# lpf-5th-order.net
KiCad netlist of a schematic drawn in EAGLE
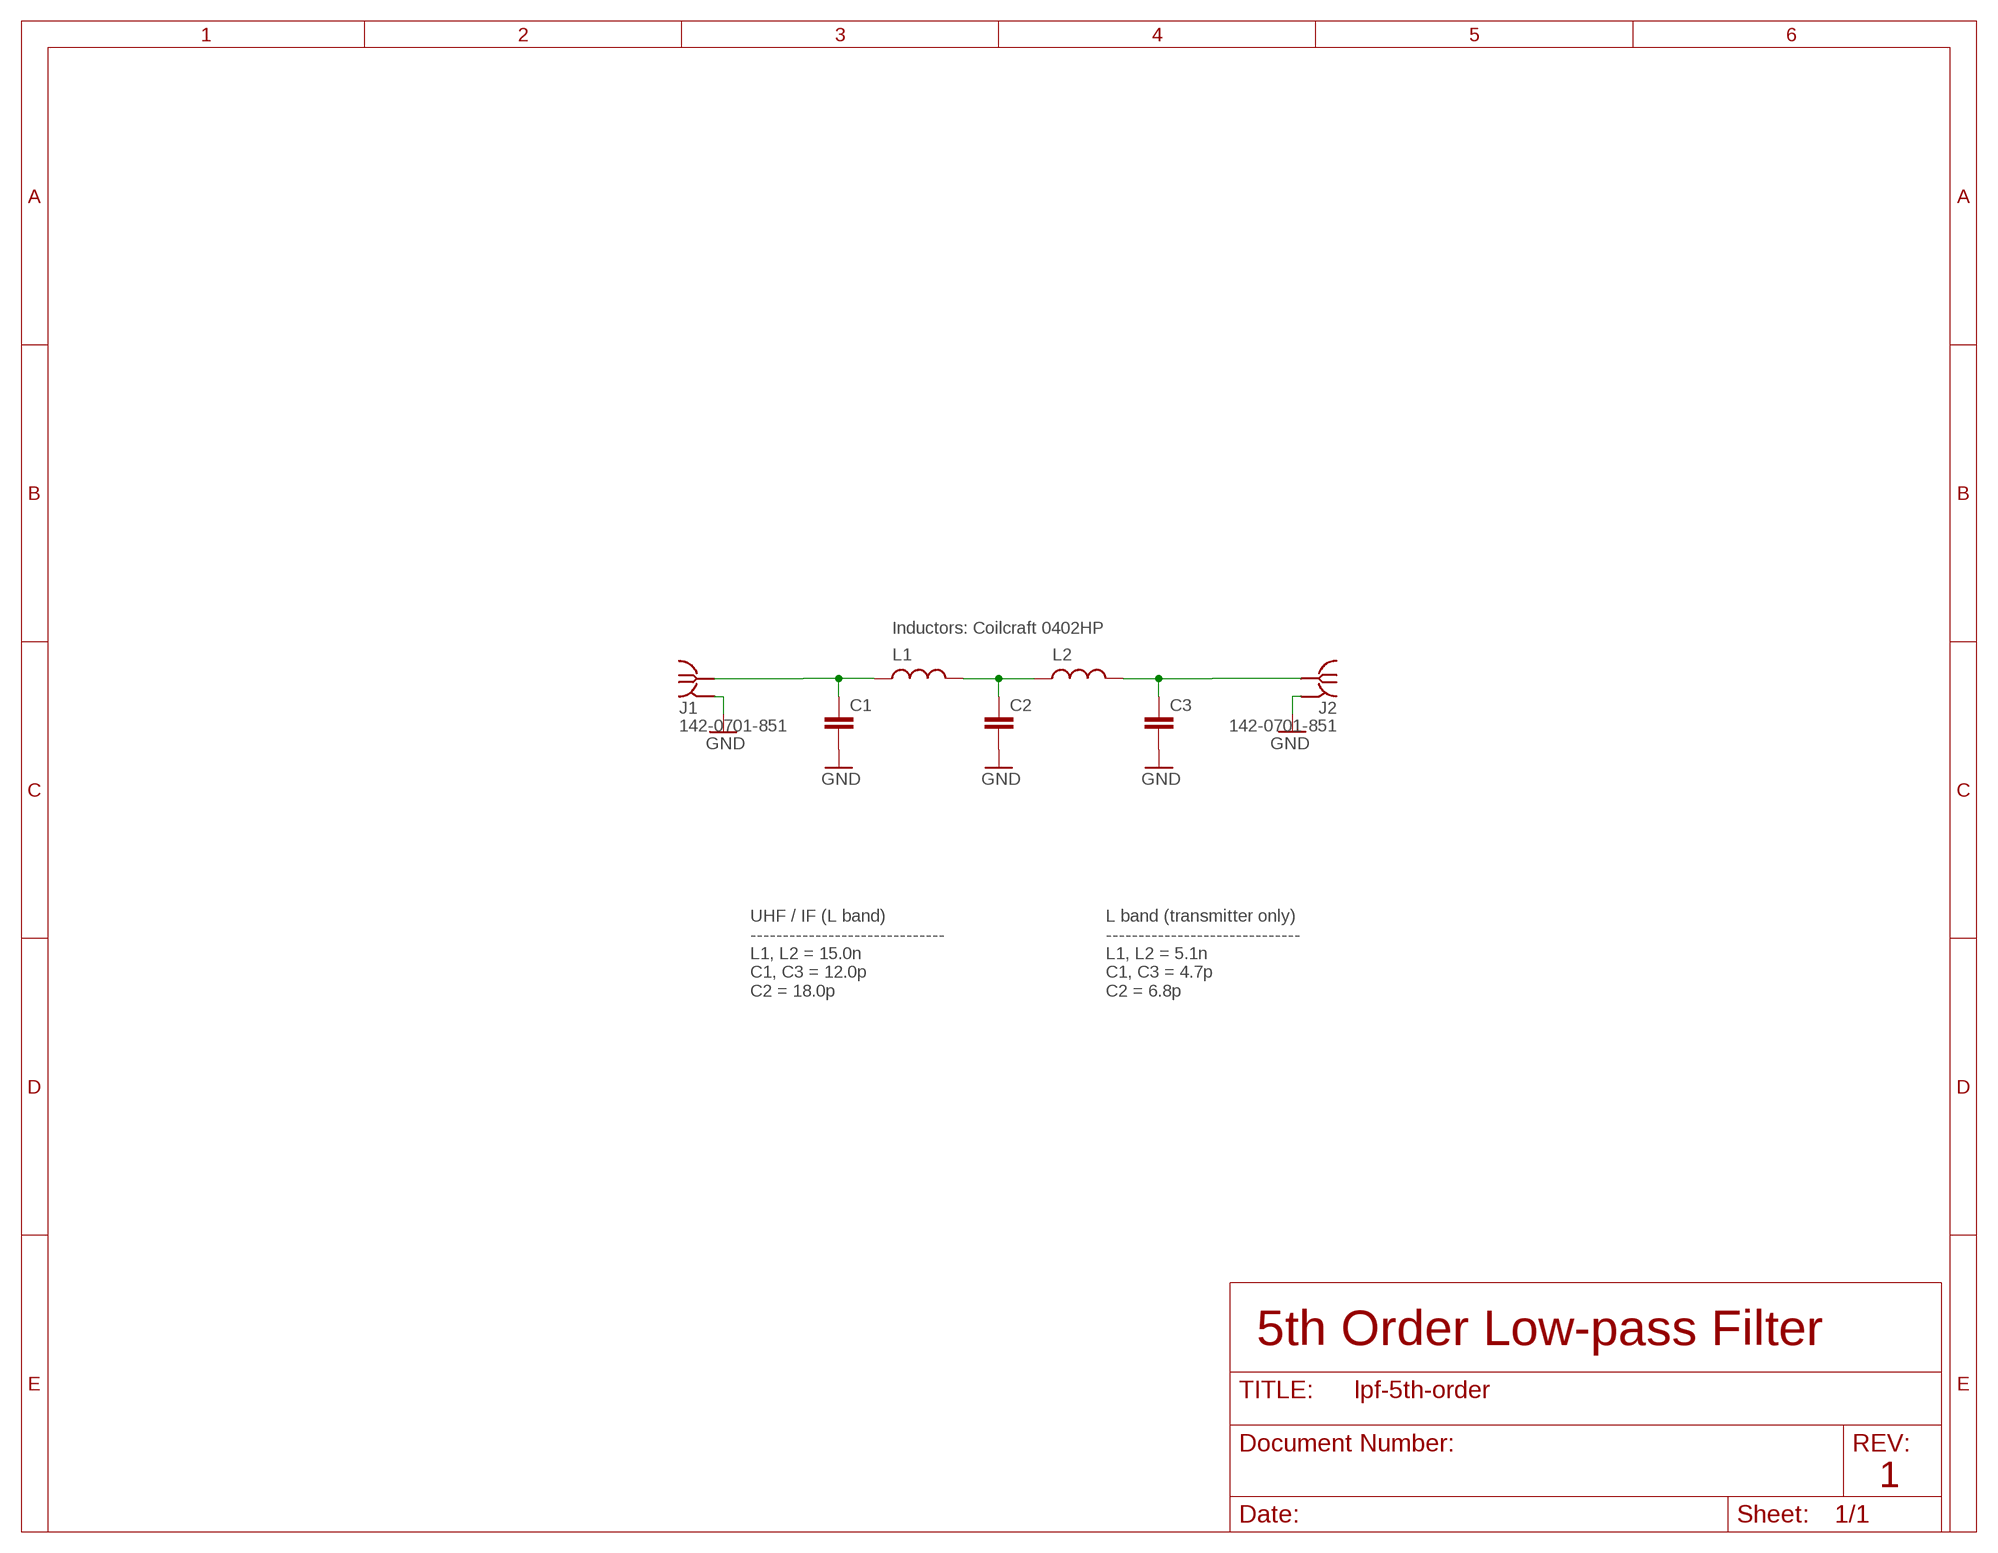
[diagram p0: schematic, sheet 1]

(export (version "E")
  (design (tool "Eeschema 10.0.6"))
  (components
    (comp (ref "C1")
      (value "C-EU0402-C-NOSILK")
      (footprint "eagle-import:.0402-C-NOSILK")
      (libsource (lib "eagle-import") (part "C-EU0402-C-NOSILK"))
    )
    (comp (ref "C2")
      (value "C-EU0402-C-NOSILK")
      (footprint "eagle-import:.0402-C-NOSILK")
      (libsource (lib "eagle-import") (part "C-EU0402-C-NOSILK"))
    )
    (comp (ref "C3")
      (value "C-EU0402-C-NOSILK")
      (footprint "eagle-import:.0402-C-NOSILK")
      (libsource (lib "eagle-import") (part "C-EU0402-C-NOSILK"))
    )
    (comp (ref "J1")
      (value "142-0701-851")
      (footprint "eagle-import:142-0701-851")
      (libsource (lib "eagle-import") (part "142-0701-851"))
    )
    (comp (ref "J2")
      (value "142-0701-851")
      (footprint "eagle-import:142-0701-851")
      (libsource (lib "eagle-import") (part "142-0701-851"))
    )
    (comp (ref "L1")
      (value "L-US0402-C-NOSILK")
      (footprint "eagle-import:.0402-C-NOSILK")
      (libsource (lib "eagle-import") (part "L-US0402-C-NOSILK"))
    )
    (comp (ref "L2")
      (value "L-US0402-C-NOSILK")
      (footprint "eagle-import:.0402-C-NOSILK")
      (libsource (lib "eagle-import") (part "L-US0402-C-NOSILK"))
    )
  )
  (nets
    (net (code "1") (name "GND") (class "Default")
      (node (ref "C1") (pin "2") (pinfunction "2_2") (pintype "passive"))
      (node (ref "C2") (pin "2") (pinfunction "2_2") (pintype "passive"))
      (node (ref "C3") (pin "2") (pinfunction "2_2") (pintype "passive"))
      (node (ref "J1") (pin "GND1") (pinfunction "GND_GND1") (pintype "bidirectional"))
      (node (ref "J1") (pin "GND2") (pinfunction "GND_GND2") (pintype "bidirectional"))
      (node (ref "J1") (pin "GND3") (pinfunction "GND_GND3") (pintype "bidirectional"))
      (node (ref "J1") (pin "GND4") (pinfunction "GND_GND4") (pintype "bidirectional"))
      (node (ref "J2") (pin "GND1") (pinfunction "GND_GND1") (pintype "bidirectional"))
      (node (ref "J2") (pin "GND2") (pinfunction "GND_GND2") (pintype "bidirectional"))
      (node (ref "J2") (pin "GND3") (pinfunction "GND_GND3") (pintype "bidirectional"))
      (node (ref "J2") (pin "GND4") (pinfunction "GND_GND4") (pintype "bidirectional"))
    )
    (net (code "2") (name "Net-(C2-Pad1)") (class "Default")
      (node (ref "C2") (pin "1") (pinfunction "1_1") (pintype "passive"))
      (node (ref "L1") (pin "2") (pinfunction "2_2") (pintype "passive"))
      (node (ref "L2") (pin "1") (pinfunction "1_1") (pintype "passive"))
    )
    (net (code "3") (name "Net-(J1-RF)") (class "Default")
      (node (ref "C1") (pin "1") (pinfunction "1_1") (pintype "passive"))
      (node (ref "J1") (pin "RF1") (pinfunction "RF_RF1") (pintype "bidirectional"))
      (node (ref "L1") (pin "1") (pinfunction "1_1") (pintype "passive"))
    )
    (net (code "4") (name "Net-(J2-RF)") (class "Default")
      (node (ref "C3") (pin "1") (pinfunction "1_1") (pintype "passive"))
      (node (ref "J2") (pin "RF1") (pinfunction "RF_RF1") (pintype "bidirectional"))
      (node (ref "L2") (pin "2") (pinfunction "2_2") (pintype "passive"))
    )
  )
)
